# splitterBoard.net
KiCad netlist of a schematic drawn in Altium Designer
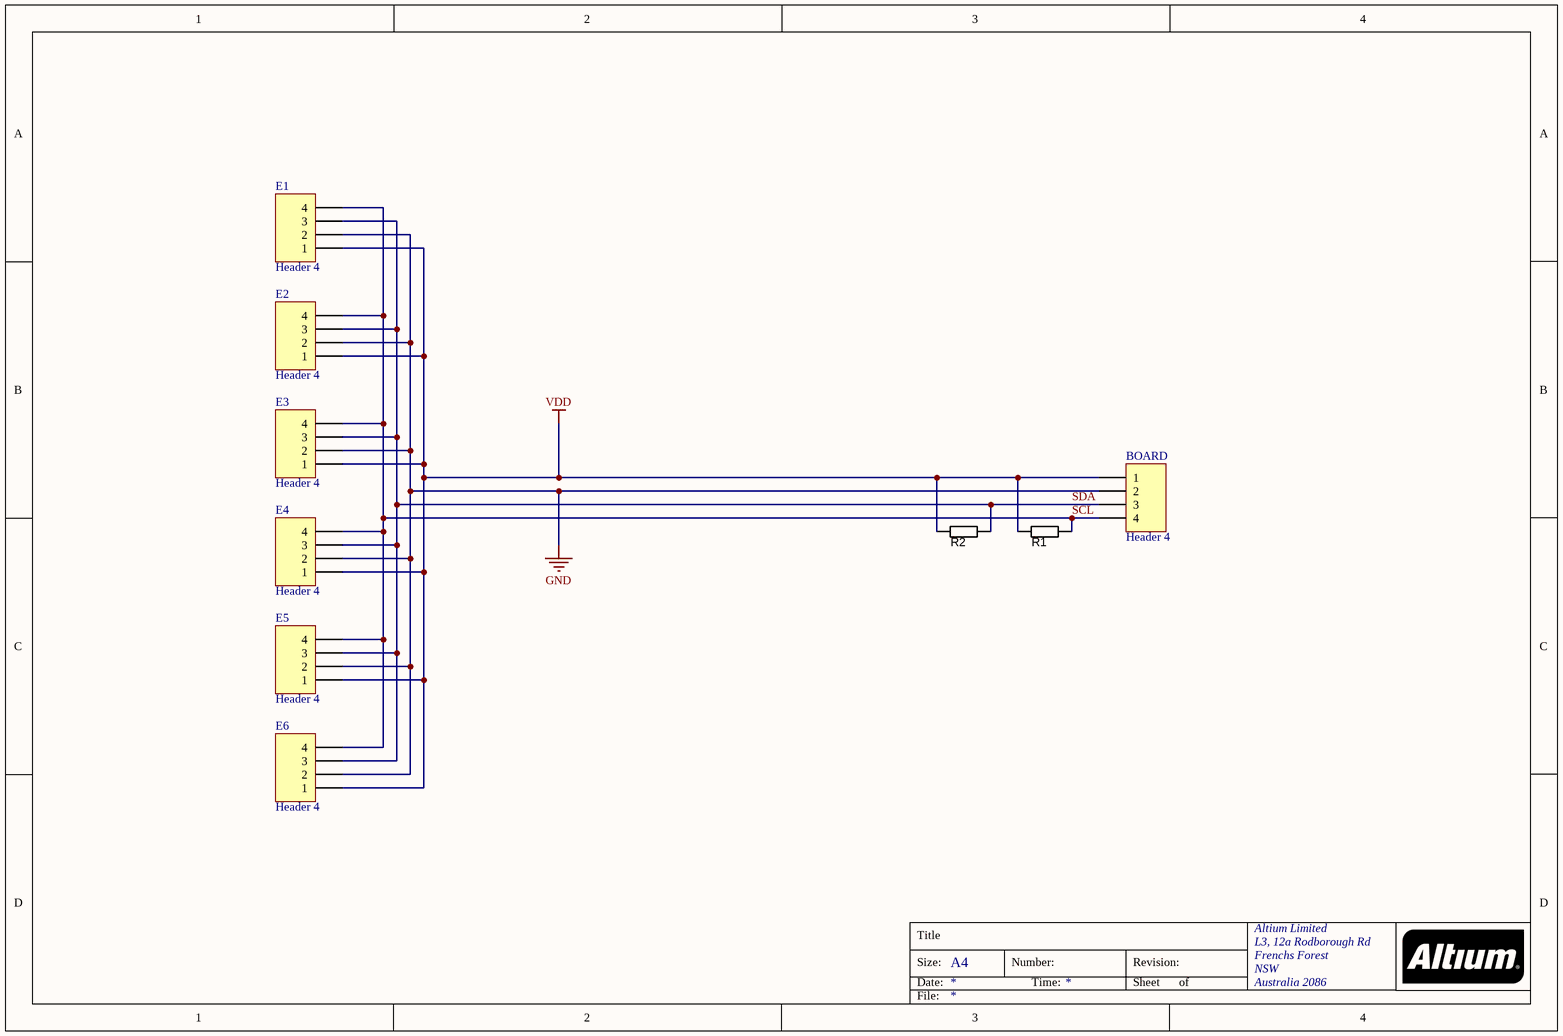
[diagram p0: splitterBoard.SchDoc]

(export (version "E")
  (design (tool "Eeschema 10.0.6"))
  (components
    (comp (ref "BOARD")
      (value "Header 4")
      (footprint "HDR1X4")
      (description "Header, 4-Pin")
      (fields (field (name "PUBLISHER") "Altium Limited"))
      (libsource (lib "") (part "Header 4_1"))
    )
    (comp (ref "E1")
      (value "Header 4")
      (footprint "HDR1X4")
      (description "Header, 4-Pin")
      (fields (field (name "PUBLISHER") "Altium Limited"))
      (libsource (lib "Miscellaneous Connectors") (part "Header 4"))
    )
    (comp (ref "E2")
      (value "Header 4")
      (footprint "HDR1X4")
      (description "Header, 4-Pin")
      (fields (field (name "PUBLISHER") "Altium Limited"))
      (libsource (lib "Miscellaneous Connectors") (part "Header 4"))
    )
    (comp (ref "E3")
      (value "Header 4")
      (footprint "HDR1X4")
      (description "Header, 4-Pin")
      (fields (field (name "PUBLISHER") "Altium Limited"))
      (libsource (lib "Miscellaneous Connectors") (part "Header 4"))
    )
    (comp (ref "E4")
      (value "Header 4")
      (footprint "HDR1X4")
      (description "Header, 4-Pin")
      (fields (field (name "PUBLISHER") "Altium Limited"))
      (libsource (lib "Miscellaneous Connectors") (part "Header 4"))
    )
    (comp (ref "E5")
      (value "Header 4")
      (footprint "HDR1X4")
      (description "Header, 4-Pin")
      (fields (field (name "PUBLISHER") "Altium Limited"))
      (libsource (lib "Miscellaneous Connectors") (part "Header 4"))
    )
    (comp (ref "E6")
      (value "Header 4")
      (footprint "HDR1X4")
      (description "Header, 4-Pin")
      (fields (field (name "PUBLISHER") "Altium Limited"))
      (libsource (lib "Miscellaneous Connectors") (part "Header 4"))
    )
    (comp (ref "R1")
      (value "RES_EMPTY_0805")
      (footprint "RESC2012X70N")
      (description "Resistor, 0805 SMD, Empty footprint")
      (libsource (lib "PBL - Resistors") (part "RES_EMPTY_0805"))
    )
    (comp (ref "R2")
      (value "RES_EMPTY_0805")
      (footprint "RESC2012X70N")
      (description "Resistor, 0805 SMD, Empty footprint")
      (libsource (lib "PBL - Resistors") (part "RES_EMPTY_0805"))
    )
  )
  (nets
    (net (code "1") (name "/SCL") (class "Default")
      (node (ref "BOARD") (pin "4") (pinfunction "4_4") (pintype "passive"))
      (node (ref "E1") (pin "4") (pinfunction "4_4") (pintype "passive"))
      (node (ref "E2") (pin "4") (pinfunction "4_4") (pintype "passive"))
      (node (ref "E3") (pin "4") (pinfunction "4_4") (pintype "passive"))
      (node (ref "E4") (pin "4") (pinfunction "4_4") (pintype "passive"))
      (node (ref "E5") (pin "4") (pinfunction "4_4") (pintype "passive"))
      (node (ref "E6") (pin "4") (pinfunction "4_4") (pintype "passive"))
      (node (ref "R1") (pin "2") (pinfunction "2_2") (pintype "passive"))
    )
    (net (code "2") (name "/SDA") (class "Default")
      (node (ref "BOARD") (pin "3") (pinfunction "3_3") (pintype "passive"))
      (node (ref "E1") (pin "3") (pinfunction "3_3") (pintype "passive"))
      (node (ref "E2") (pin "3") (pinfunction "3_3") (pintype "passive"))
      (node (ref "E3") (pin "3") (pinfunction "3_3") (pintype "passive"))
      (node (ref "E4") (pin "3") (pinfunction "3_3") (pintype "passive"))
      (node (ref "E5") (pin "3") (pinfunction "3_3") (pintype "passive"))
      (node (ref "E6") (pin "3") (pinfunction "3_3") (pintype "passive"))
      (node (ref "R2") (pin "2") (pinfunction "2_2") (pintype "passive"))
    )
    (net (code "3") (name "GND") (class "Default")
      (node (ref "BOARD") (pin "2") (pinfunction "2_2") (pintype "passive"))
      (node (ref "E1") (pin "2") (pinfunction "2_2") (pintype "passive"))
      (node (ref "E2") (pin "2") (pinfunction "2_2") (pintype "passive"))
      (node (ref "E3") (pin "2") (pinfunction "2_2") (pintype "passive"))
      (node (ref "E4") (pin "2") (pinfunction "2_2") (pintype "passive"))
      (node (ref "E5") (pin "2") (pinfunction "2_2") (pintype "passive"))
      (node (ref "E6") (pin "2") (pinfunction "2_2") (pintype "passive"))
    )
    (net (code "4") (name "VDD") (class "Default")
      (node (ref "BOARD") (pin "1") (pinfunction "1_1") (pintype "passive"))
      (node (ref "E1") (pin "1") (pinfunction "1_1") (pintype "passive"))
      (node (ref "E2") (pin "1") (pinfunction "1_1") (pintype "passive"))
      (node (ref "E3") (pin "1") (pinfunction "1_1") (pintype "passive"))
      (node (ref "E4") (pin "1") (pinfunction "1_1") (pintype "passive"))
      (node (ref "E5") (pin "1") (pinfunction "1_1") (pintype "passive"))
      (node (ref "E6") (pin "1") (pinfunction "1_1") (pintype "passive"))
      (node (ref "R1") (pin "1") (pinfunction "1_1") (pintype "passive"))
      (node (ref "R2") (pin "1") (pinfunction "1_1") (pintype "passive"))
    )
  )
)
